# EPS_Temperature-Sensor.net
KiCad netlist of a schematic drawn in Altium Designer
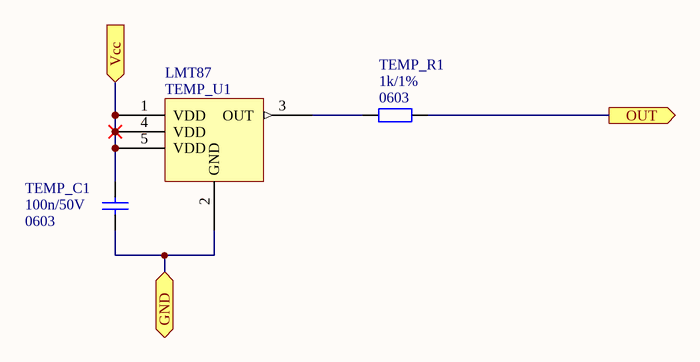
[diagram p0: EPS_Temperature-Sensor.SchDoc]

(export (version "E")
  (design (tool "Eeschema 10.0.6"))
  (components
    (comp (ref "TEMP_C1")
      (value "100n/50V")
      (footprint "SMD_Capacitor_0603")
      (description "Ceramic Cap Kemet COTS 100n/50V X7R 0603")
      (fields
        (field (name "MANUFACTURER") "Kemet")
        (field (name "MANUFACTURERPARTNUMBER") "C0603T104K5RALTU")
        (field (name "PACKAGE") "0603")
      )
      (libsource (lib "capacitors") (part "Cer_C0603T104K5RALTU"))
    )
    (comp (ref "TEMP_R1")
      (value "1k/1%")
      (footprint "SMD_Resistor_0603")
      (description "1k/1% Vishay CRCW 0603 Resistor. 100mW, 100ppm, 75V.")
      (fields
        (field (name "MANUFACTURER") "Vishay")
        (field (name "MANUFACTURERPARTNUMBER") "CRCW06031K00FKxxxx")
        (field (name "PACKAGE") "0603")
      )
      (libsource (lib "resistors") (part "CRCW06031K00FKxxxx"))
    )
    (comp (ref "TEMP_U1")
      (value "LMT87")
      (footprint "SC70-LT5_N")
      (description "Analog Temperature Sensors with Class-AB Output")
      (libsource (lib "microcircuits") (part "LMT87"))
    )
  )
  (nets
    (net (code "1") (name "/GND") (class "Default")
      (node (ref "TEMP_C1") (pin "2") (pinfunction "2_2") (pintype "passive"))
      (node (ref "TEMP_U1") (pin "2") (pinfunction "GND_2") (pintype "power_in"))
    )
    (net (code "2") (name "/OUT") (class "Default")
      (node (ref "TEMP_R1") (pin "2") (pinfunction "2_2") (pintype "passive"))
    )
    (net (code "3") (name "/Vcc") (class "Default")
      (node (ref "TEMP_C1") (pin "1") (pinfunction "1_1") (pintype "passive"))
      (node (ref "TEMP_U1") (pin "1") (pinfunction "VDD_1") (pintype "passive"))
      (node (ref "TEMP_U1") (pin "4") (pinfunction "VDD_4") (pintype "power_in"))
      (node (ref "TEMP_U1") (pin "5") (pinfunction "VDD_5") (pintype "power_in"))
    )
    (net (code "4") (name "Net-(TEMP_U1-OUT)") (class "Default")
      (node (ref "TEMP_R1") (pin "1") (pinfunction "1_1") (pintype "passive"))
      (node (ref "TEMP_U1") (pin "3") (pinfunction "OUT_3") (pintype "output"))
    )
  )
)
